# PCB.net
KiCad netlist of a schematic drawn in EAGLE
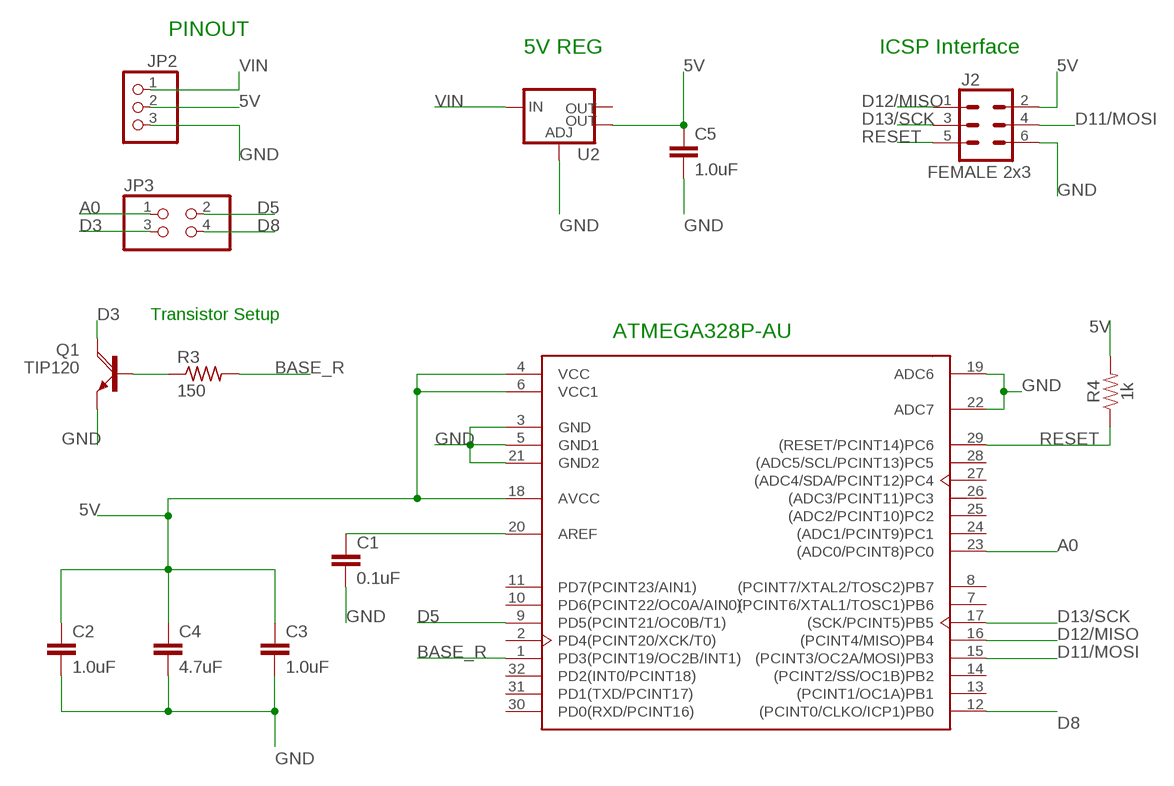
[diagram p0: schematic, sheet 1]

(export (version "E")
  (design (tool "Eeschema 10.0.6"))
  (components
    (comp (ref "C1")
      (value "0.1uF")
      (footprint "eagle-import:0603")
      (libsource (lib "eagle-import") (part "0.1UF-0603-25V-(+80/-20%)"))
    )
    (comp (ref "C2")
      (value "1.0uF")
      (footprint "eagle-import:0603")
      (libsource (lib "eagle-import") (part "1.0UF-0603-16V-10%"))
    )
    (comp (ref "C3")
      (value "1.0uF")
      (footprint "eagle-import:0603")
      (libsource (lib "eagle-import") (part "1.0UF-0603-16V-10%"))
    )
    (comp (ref "C4")
      (value "4.7uF")
      (footprint "eagle-import:1206")
      (libsource (lib "eagle-import") (part "4.7UF-1206-16V-(+80/-20%)"))
    )
    (comp (ref "C5")
      (value "1.0uF")
      (footprint "eagle-import:0603")
      (libsource (lib "eagle-import") (part "1.0UF-0603-16V-10%"))
    )
    (comp (ref "J2")
      (value "FEMALE 2x3")
      (footprint "eagle-import:2X3")
      (libsource (lib "eagle-import") (part "CONN_03X2FEMALE"))
    )
    (comp (ref "JP2")
      (value "PINHEAD_PINHD-1X3")
      (footprint "eagle-import:PINHEAD_1X03")
      (libsource (lib "eagle-import") (part "PINHEAD_PINHD-1X3"))
    )
    (comp (ref "JP3")
      (value "PINHD-2X2")
      (footprint "eagle-import:2X02")
      (libsource (lib "eagle-import") (part "PINHD-2X2"))
    )
    (comp (ref "Q1")
      (value "TIP120")
      (footprint "eagle-import:TO220AH")
      (libsource (lib "eagle-import") (part "TIP120"))
    )
    (comp (ref "R3")
      (value "150")
      (footprint "eagle-import:R0805")
      (libsource (lib "eagle-import") (part "R-US_R0805"))
    )
    (comp (ref "R4")
      (value "1k")
      (footprint "eagle-import:0603")
      (libsource (lib "eagle-import") (part "1KOHM-0603-1/10W-1%"))
    )
    (comp (ref "U1")
      (value "ATMEGA328P-AU")
      (footprint "eagle-import:TQFP-32")
      (fields
        (field (name "DIGIKEY_PART_NUMBER") "ATMEGA328P-AU-ND")
        (field (name "MANUFACTURER") "Microchip Technology")
        (field (name "CREATED_BY") "PCBLayout.com")
      )
      (libsource (lib "eagle-import") (part "ATMEGA328P-AU"))
    )
    (comp (ref "U2")
      (value "V_REG_LM1117SOT223")
      (footprint "eagle-import:SOT223")
      (libsource (lib "eagle-import") (part "V_REG_LM1117SOT223"))
    )
  )
  (nets
    (net (code "1") (name "/5V") (class "Default")
      (node (ref "C2") (pin "1") (pinfunction "1_1") (pintype "passive"))
      (node (ref "C3") (pin "1") (pinfunction "1_1") (pintype "passive"))
      (node (ref "C4") (pin "1") (pinfunction "1_1") (pintype "passive"))
      (node (ref "C5") (pin "1") (pinfunction "1_1") (pintype "passive"))
      (node (ref "J2") (pin "2") (pinfunction "2_2") (pintype "bidirectional"))
      (node (ref "JP2") (pin "2") (pinfunction "2_2") (pintype "passive"))
      (node (ref "R4") (pin "2") (pinfunction "2_2") (pintype "passive"))
      (node (ref "U1") (pin "18") (pinfunction "AVCC_18") (pintype "power_in"))
      (node (ref "U1") (pin "4") (pinfunction "VCC_4") (pintype "power_in"))
      (node (ref "U1") (pin "6") (pinfunction "VCC1_6") (pintype "power_in"))
      (node (ref "U2") (pin "4") (pinfunction "OUT_4") (pintype "output"))
    )
    (net (code "2") (name "/A0") (class "Default")
      (node (ref "JP3") (pin "1") (pinfunction "1_1") (pintype "passive"))
      (node (ref "U1") (pin "23") (pinfunction "(ADC0/PCINT8)PC0_23") (pintype "bidirectional"))
    )
    (net (code "3") (name "/BASE_R") (class "Default")
      (node (ref "R3") (pin "2") (pinfunction "2_2") (pintype "passive"))
      (node (ref "U1") (pin "1") (pinfunction "PD3(PCINT19/OC2B/INT1)_1") (pintype "bidirectional"))
    )
    (net (code "4") (name "/D3") (class "Default")
      (node (ref "JP3") (pin "3") (pinfunction "3_3") (pintype "passive"))
      (node (ref "Q1") (pin "C") (pinfunction "C_C") (pintype "passive"))
    )
    (net (code "5") (name "/D5") (class "Default")
      (node (ref "JP3") (pin "2") (pinfunction "2_2") (pintype "passive"))
      (node (ref "U1") (pin "9") (pinfunction "PD5(PCINT21/OC0B/T1)_9") (pintype "bidirectional"))
    )
    (net (code "6") (name "/D8") (class "Default")
      (node (ref "JP3") (pin "4") (pinfunction "4_4") (pintype "passive"))
      (node (ref "U1") (pin "12") (pinfunction "(PCINT0/CLKO/ICP1)PB0_12") (pintype "bidirectional"))
    )
    (net (code "7") (name "/D11{slash}MOSI") (class "Default")
      (node (ref "J2") (pin "4") (pinfunction "4_4") (pintype "bidirectional"))
      (node (ref "U1") (pin "15") (pinfunction "(PCINT3/OC2A/MOSI)PB3_15") (pintype "bidirectional"))
    )
    (net (code "8") (name "/D12{slash}MISO") (class "Default")
      (node (ref "J2") (pin "1") (pinfunction "1_1") (pintype "bidirectional"))
      (node (ref "U1") (pin "16") (pinfunction "(PCINT4/MISO)PB4_16") (pintype "bidirectional"))
    )
    (net (code "9") (name "/D13{slash}SCK") (class "Default")
      (node (ref "J2") (pin "3") (pinfunction "3_3") (pintype "bidirectional"))
      (node (ref "U1") (pin "17") (pinfunction "(SCK/PCINT5)PB5_17") (pintype "bidirectional"))
    )
    (net (code "10") (name "/GND") (class "Default")
      (node (ref "C1") (pin "2") (pinfunction "2_2") (pintype "passive"))
      (node (ref "C2") (pin "2") (pinfunction "2_2") (pintype "passive"))
      (node (ref "C3") (pin "2") (pinfunction "2_2") (pintype "passive"))
      (node (ref "C4") (pin "2") (pinfunction "2_2") (pintype "passive"))
      (node (ref "C5") (pin "2") (pinfunction "2_2") (pintype "passive"))
      (node (ref "J2") (pin "6") (pinfunction "6_6") (pintype "bidirectional"))
      (node (ref "JP2") (pin "3") (pinfunction "3_3") (pintype "passive"))
      (node (ref "Q1") (pin "E") (pinfunction "E_E") (pintype "passive"))
      (node (ref "U1") (pin "19") (pinfunction "ADC6_19") (pintype "input"))
      (node (ref "U1") (pin "21") (pinfunction "GND2_21") (pintype "power_in"))
      (node (ref "U1") (pin "22") (pinfunction "ADC7_22") (pintype "input"))
      (node (ref "U1") (pin "3") (pinfunction "GND_3") (pintype "power_in"))
      (node (ref "U1") (pin "5") (pinfunction "GND1_5") (pintype "power_in"))
      (node (ref "U2") (pin "1") (pinfunction "ADJ_1") (pintype "input"))
    )
    (net (code "11") (name "/RESET") (class "Default")
      (node (ref "J2") (pin "5") (pinfunction "5_5") (pintype "bidirectional"))
      (node (ref "R4") (pin "1") (pinfunction "1_1") (pintype "passive"))
      (node (ref "U1") (pin "29") (pinfunction "(RESET/PCINT14)PC6_29") (pintype "bidirectional"))
    )
    (net (code "12") (name "/VIN") (class "Default")
      (node (ref "JP2") (pin "1") (pinfunction "1_1") (pintype "passive"))
      (node (ref "U2") (pin "3") (pinfunction "IN_3") (pintype "input"))
    )
    (net (code "13") (name "Net-(Q1-PadB)") (class "Default")
      (node (ref "Q1") (pin "B") (pinfunction "B_B") (pintype "passive"))
      (node (ref "R3") (pin "1") (pinfunction "1_1") (pintype "passive"))
    )
    (net (code "14") (name "Net-(U1-AREF)") (class "Default")
      (node (ref "C1") (pin "1") (pinfunction "1_1") (pintype "passive"))
      (node (ref "U1") (pin "20") (pinfunction "AREF_20") (pintype "power_in"))
    )
    (net (code "15") (name "unconnected-(U1-(ADC1{slash}PCINT9)PC1-Pad24)") (class "Default")
      (node (ref "U1") (pin "24") (pinfunction "(ADC1/PCINT9)PC1_24") (pintype "bidirectional"))
    )
    (net (code "16") (name "unconnected-(U1-(ADC2{slash}PCINT10)PC2-Pad25)") (class "Default")
      (node (ref "U1") (pin "25") (pinfunction "(ADC2/PCINT10)PC2_25") (pintype "bidirectional"))
    )
    (net (code "17") (name "unconnected-(U1-(ADC3{slash}PCINT11)PC3-Pad26)") (class "Default")
      (node (ref "U1") (pin "26") (pinfunction "(ADC3/PCINT11)PC3_26") (pintype "bidirectional"))
    )
    (net (code "18") (name "unconnected-(U1-(ADC4{slash}SDA{slash}PCINT12)PC4-Pad27)") (class "Default")
      (node (ref "U1") (pin "27") (pinfunction "(ADC4/SDA/PCINT12)PC4_27") (pintype "bidirectional"))
    )
    (net (code "19") (name "unconnected-(U1-(ADC5{slash}SCL{slash}PCINT13)PC5-Pad28)") (class "Default")
      (node (ref "U1") (pin "28") (pinfunction "(ADC5/SCL/PCINT13)PC5_28") (pintype "bidirectional"))
    )
    (net (code "20") (name "unconnected-(U1-(PCINT1{slash}OC1A)PB1-Pad13)") (class "Default")
      (node (ref "U1") (pin "13") (pinfunction "(PCINT1/OC1A)PB1_13") (pintype "bidirectional"))
    )
    (net (code "21") (name "unconnected-(U1-(PCINT2{slash}SS{slash}OC1B)PB2-Pad14)") (class "Default")
      (node (ref "U1") (pin "14") (pinfunction "(PCINT2/SS/OC1B)PB2_14") (pintype "bidirectional"))
    )
    (net (code "22") (name "unconnected-(U1-(PCINT6{slash}XTAL1{slash}TOSC1)PB6-Pad7)") (class "Default")
      (node (ref "U1") (pin "7") (pinfunction "(PCINT6/XTAL1/TOSC1)PB6_7") (pintype "bidirectional"))
    )
    (net (code "23") (name "unconnected-(U1-(PCINT7{slash}XTAL2{slash}TOSC2)PB7-Pad8)") (class "Default")
      (node (ref "U1") (pin "8") (pinfunction "(PCINT7/XTAL2/TOSC2)PB7_8") (pintype "bidirectional"))
    )
    (net (code "24") (name "unconnected-(U1-PD0(RXD{slash}PCINT16)-Pad30)") (class "Default")
      (node (ref "U1") (pin "30") (pinfunction "PD0(RXD/PCINT16)_30") (pintype "bidirectional"))
    )
    (net (code "25") (name "unconnected-(U1-PD1(TXD{slash}PCINT17)-Pad31)") (class "Default")
      (node (ref "U1") (pin "31") (pinfunction "PD1(TXD/PCINT17)_31") (pintype "bidirectional"))
    )
    (net (code "26") (name "unconnected-(U1-PD2(INT0{slash}PCINT18)-Pad32)") (class "Default")
      (node (ref "U1") (pin "32") (pinfunction "PD2(INT0/PCINT18)_32") (pintype "bidirectional"))
    )
    (net (code "27") (name "unconnected-(U1-PD4(PCINT20{slash}XCK{slash}T0)-Pad2)") (class "Default")
      (node (ref "U1") (pin "2") (pinfunction "PD4(PCINT20/XCK/T0)_2") (pintype "bidirectional"))
    )
    (net (code "28") (name "unconnected-(U1-PD6(PCINT22{slash}OC0A{slash}AIN0)-Pad10)") (class "Default")
      (node (ref "U1") (pin "10") (pinfunction "PD6(PCINT22/OC0A/AIN0)_10") (pintype "bidirectional"))
    )
    (net (code "29") (name "unconnected-(U1-PD7(PCINT23{slash}AIN1)-Pad11)") (class "Default")
      (node (ref "U1") (pin "11") (pinfunction "PD7(PCINT23/AIN1)_11") (pintype "bidirectional"))
    )
    (net (code "30") (name "unconnected-(U2-OUT-Pad2)") (class "Default")
      (node (ref "U2") (pin "2") (pinfunction "OUT_2") (pintype "output"))
    )
  )
)
